# 2AND_2.net
KiCad netlist of a schematic drawn in EAGLE
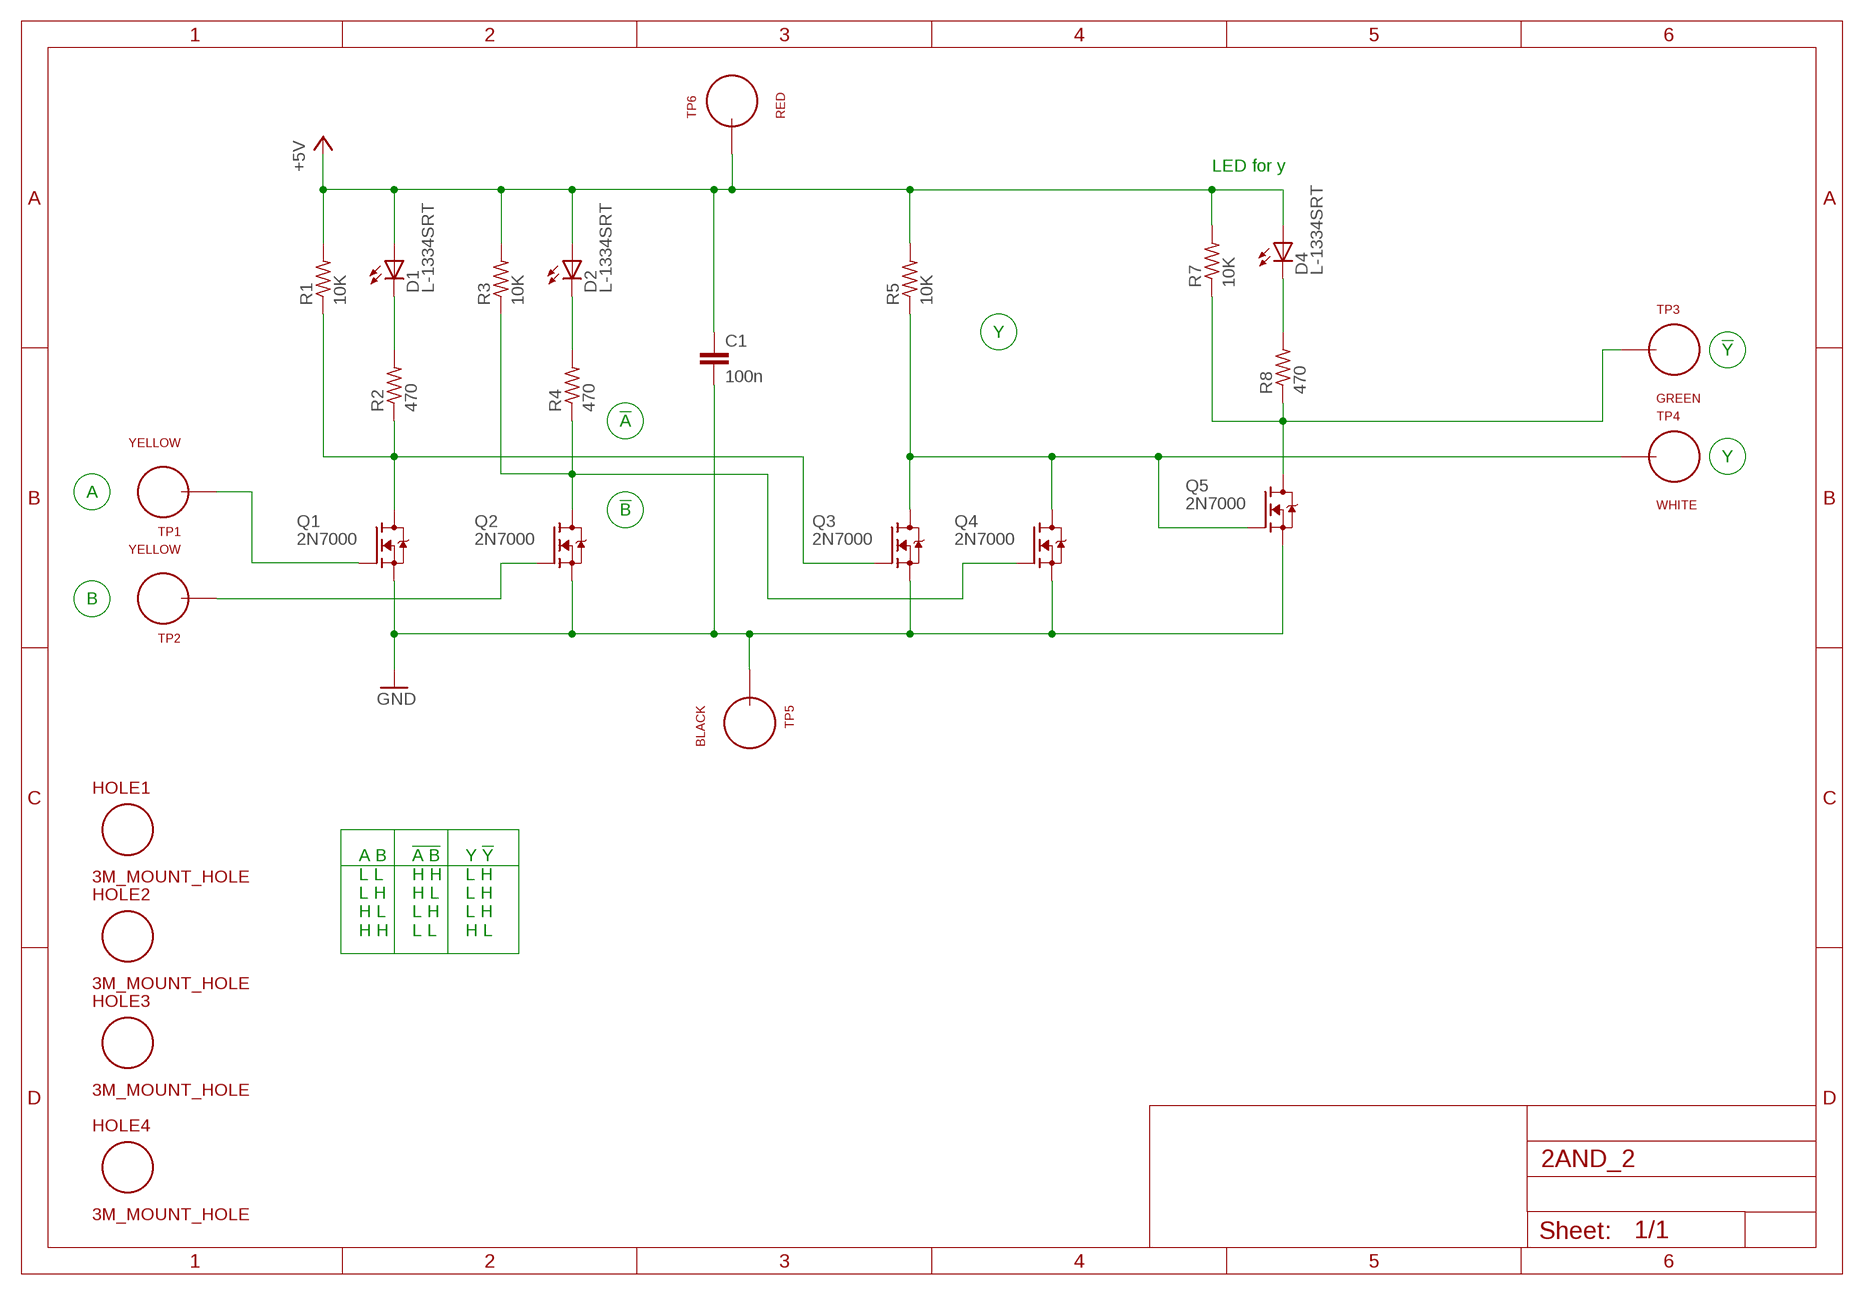
[diagram p0: schematic, sheet 1]

(export (version "E")
  (design (tool "Eeschema 10.0.6"))
  (components
    (comp (ref "C1")
      (value "100n")
      (footprint "eagle-import:CAP_P2INCH")
      (libsource (lib "eagle-import") (part "C_P2INCH"))
    )
    (comp (ref "D1")
      (value "L-1334SRT")
      (footprint "eagle-import:LED3MM")
      (libsource (lib "eagle-import") (part "L-1334SRT"))
    )
    (comp (ref "D2")
      (value "L-1334SRT")
      (footprint "eagle-import:LED3MM")
      (libsource (lib "eagle-import") (part "L-1334SRT"))
    )
    (comp (ref "D4")
      (value "L-1334SRT")
      (footprint "eagle-import:LED3MM")
      (libsource (lib "eagle-import") (part "L-1334SRT"))
    )
    (comp (ref "HOLE1")
      (value "3M_MOUNT_HOLE")
      (footprint "eagle-import:3M_HOLE")
      (libsource (lib "eagle-import") (part "3M_MOUNT_HOLE"))
    )
    (comp (ref "HOLE2")
      (value "3M_MOUNT_HOLE")
      (footprint "eagle-import:3M_HOLE")
      (libsource (lib "eagle-import") (part "3M_MOUNT_HOLE"))
    )
    (comp (ref "HOLE3")
      (value "3M_MOUNT_HOLE")
      (footprint "eagle-import:3M_HOLE")
      (libsource (lib "eagle-import") (part "3M_MOUNT_HOLE"))
    )
    (comp (ref "HOLE4")
      (value "3M_MOUNT_HOLE")
      (footprint "eagle-import:3M_HOLE")
      (libsource (lib "eagle-import") (part "3M_MOUNT_HOLE"))
    )
    (comp (ref "Q1")
      (value "2N7000")
      (footprint "eagle-import:TO92-DGS")
      (libsource (lib "eagle-import") (part "2N7000"))
    )
    (comp (ref "Q2")
      (value "2N7000")
      (footprint "eagle-import:TO92-DGS")
      (libsource (lib "eagle-import") (part "2N7000"))
    )
    (comp (ref "Q3")
      (value "2N7000")
      (footprint "eagle-import:TO92-DGS")
      (libsource (lib "eagle-import") (part "2N7000"))
    )
    (comp (ref "Q4")
      (value "2N7000")
      (footprint "eagle-import:TO92-DGS")
      (libsource (lib "eagle-import") (part "2N7000"))
    )
    (comp (ref "Q5")
      (value "2N7000")
      (footprint "eagle-import:TO92-DGS")
      (libsource (lib "eagle-import") (part "2N7000"))
    )
    (comp (ref "R1")
      (value "10K")
      (footprint "eagle-import:R_P2INCH")
      (libsource (lib "eagle-import") (part "R_P2INCH"))
    )
    (comp (ref "R2")
      (value "470")
      (footprint "eagle-import:R_P2INCH")
      (libsource (lib "eagle-import") (part "R_P2INCH"))
    )
    (comp (ref "R3")
      (value "10K")
      (footprint "eagle-import:R_P2INCH")
      (libsource (lib "eagle-import") (part "R_P2INCH"))
    )
    (comp (ref "R4")
      (value "470")
      (footprint "eagle-import:R_P2INCH")
      (libsource (lib "eagle-import") (part "R_P2INCH"))
    )
    (comp (ref "R5")
      (value "10K")
      (footprint "eagle-import:R_P2INCH")
      (libsource (lib "eagle-import") (part "R_P2INCH"))
    )
    (comp (ref "R7")
      (value "10K")
      (footprint "eagle-import:R_P2INCH")
      (libsource (lib "eagle-import") (part "R_P2INCH"))
    )
    (comp (ref "R8")
      (value "470")
      (footprint "eagle-import:R_P2INCH")
      (libsource (lib "eagle-import") (part "R_P2INCH"))
    )
    (comp (ref "TP1")
      (value "YELLOW")
      (footprint "eagle-import:TEST_LOOP")
      (libsource (lib "eagle-import") (part "TEST_LOOP"))
    )
    (comp (ref "TP2")
      (value "YELLOW")
      (footprint "eagle-import:TEST_LOOP")
      (libsource (lib "eagle-import") (part "TEST_LOOP"))
    )
    (comp (ref "TP3")
      (value "GREEN")
      (footprint "eagle-import:TEST_LOOP")
      (libsource (lib "eagle-import") (part "TEST_LOOP"))
    )
    (comp (ref "TP4")
      (value "WHITE")
      (footprint "eagle-import:TEST_LOOP")
      (libsource (lib "eagle-import") (part "TEST_LOOP"))
    )
    (comp (ref "TP5")
      (value "BLACK")
      (footprint "eagle-import:TEST_LOOP")
      (libsource (lib "eagle-import") (part "TEST_LOOP"))
    )
    (comp (ref "TP6")
      (value "RED")
      (footprint "eagle-import:TEST_LOOP")
      (libsource (lib "eagle-import") (part "TEST_LOOP"))
    )
  )
  (nets
    (net (code "1") (name "+5V") (class "Default")
      (node (ref "C1") (pin "1") (pinfunction "1_1") (pintype "passive"))
      (node (ref "D1") (pin "A") (pinfunction "A_A") (pintype "passive"))
      (node (ref "D2") (pin "A") (pinfunction "A_A") (pintype "passive"))
      (node (ref "D4") (pin "A") (pinfunction "A_A") (pintype "passive"))
      (node (ref "R1") (pin "2") (pinfunction "2_2") (pintype "passive"))
      (node (ref "R3") (pin "2") (pinfunction "2_2") (pintype "passive"))
      (node (ref "R5") (pin "2") (pinfunction "2_2") (pintype "passive"))
      (node (ref "R7") (pin "2") (pinfunction "2_2") (pintype "passive"))
      (node (ref "TP6") (pin "P$1") (pinfunction "P$1_P$1") (pintype "bidirectional"))
    )
    (net (code "2") (name "GND") (class "Default")
      (node (ref "C1") (pin "2") (pinfunction "2_2") (pintype "passive"))
      (node (ref "Q1") (pin "S") (pinfunction "S_S") (pintype "passive"))
      (node (ref "Q2") (pin "S") (pinfunction "S_S") (pintype "passive"))
      (node (ref "Q3") (pin "S") (pinfunction "S_S") (pintype "passive"))
      (node (ref "Q4") (pin "S") (pinfunction "S_S") (pintype "passive"))
      (node (ref "Q5") (pin "S") (pinfunction "S_S") (pintype "passive"))
      (node (ref "TP5") (pin "P$1") (pinfunction "P$1_P$1") (pintype "bidirectional"))
    )
    (net (code "3") (name "Net-(D1-C)") (class "Default")
      (node (ref "D1") (pin "K") (pinfunction "C_K") (pintype "passive"))
      (node (ref "R2") (pin "2") (pinfunction "2_2") (pintype "passive"))
    )
    (net (code "4") (name "Net-(D2-C)") (class "Default")
      (node (ref "D2") (pin "K") (pinfunction "C_K") (pintype "passive"))
      (node (ref "R4") (pin "2") (pinfunction "2_2") (pintype "passive"))
    )
    (net (code "5") (name "Net-(D4-C)") (class "Default")
      (node (ref "D4") (pin "K") (pinfunction "C_K") (pintype "passive"))
      (node (ref "R8") (pin "2") (pinfunction "2_2") (pintype "passive"))
    )
    (net (code "6") (name "Net-(Q1-PadD)") (class "Default")
      (node (ref "Q1") (pin "D") (pinfunction "D_D") (pintype "passive"))
      (node (ref "Q3") (pin "G") (pinfunction "G_G") (pintype "passive"))
      (node (ref "R1") (pin "1") (pinfunction "1_1") (pintype "passive"))
      (node (ref "R2") (pin "1") (pinfunction "1_1") (pintype "passive"))
    )
    (net (code "7") (name "Net-(Q1-PadG)") (class "Default")
      (node (ref "Q1") (pin "G") (pinfunction "G_G") (pintype "passive"))
      (node (ref "TP1") (pin "P$1") (pinfunction "P$1_P$1") (pintype "bidirectional"))
    )
    (net (code "8") (name "Net-(Q2-PadD)") (class "Default")
      (node (ref "Q2") (pin "D") (pinfunction "D_D") (pintype "passive"))
      (node (ref "Q4") (pin "G") (pinfunction "G_G") (pintype "passive"))
      (node (ref "R3") (pin "1") (pinfunction "1_1") (pintype "passive"))
      (node (ref "R4") (pin "1") (pinfunction "1_1") (pintype "passive"))
    )
    (net (code "9") (name "Net-(Q2-PadG)") (class "Default")
      (node (ref "Q2") (pin "G") (pinfunction "G_G") (pintype "passive"))
      (node (ref "TP2") (pin "P$1") (pinfunction "P$1_P$1") (pintype "bidirectional"))
    )
    (net (code "10") (name "Net-(Q3-PadD)") (class "Default")
      (node (ref "Q3") (pin "D") (pinfunction "D_D") (pintype "passive"))
      (node (ref "Q4") (pin "D") (pinfunction "D_D") (pintype "passive"))
      (node (ref "Q5") (pin "G") (pinfunction "G_G") (pintype "passive"))
      (node (ref "R5") (pin "1") (pinfunction "1_1") (pintype "passive"))
      (node (ref "TP4") (pin "P$1") (pinfunction "P$1_P$1") (pintype "bidirectional"))
    )
    (net (code "11") (name "Net-(Q5-PadD)") (class "Default")
      (node (ref "Q5") (pin "D") (pinfunction "D_D") (pintype "passive"))
      (node (ref "R7") (pin "1") (pinfunction "1_1") (pintype "passive"))
      (node (ref "R8") (pin "1") (pinfunction "1_1") (pintype "passive"))
      (node (ref "TP3") (pin "P$1") (pinfunction "P$1_P$1") (pintype "bidirectional"))
    )
  )
)
